# MysensorsDimmer.net
KiCad netlist of a schematic drawn in EAGLE
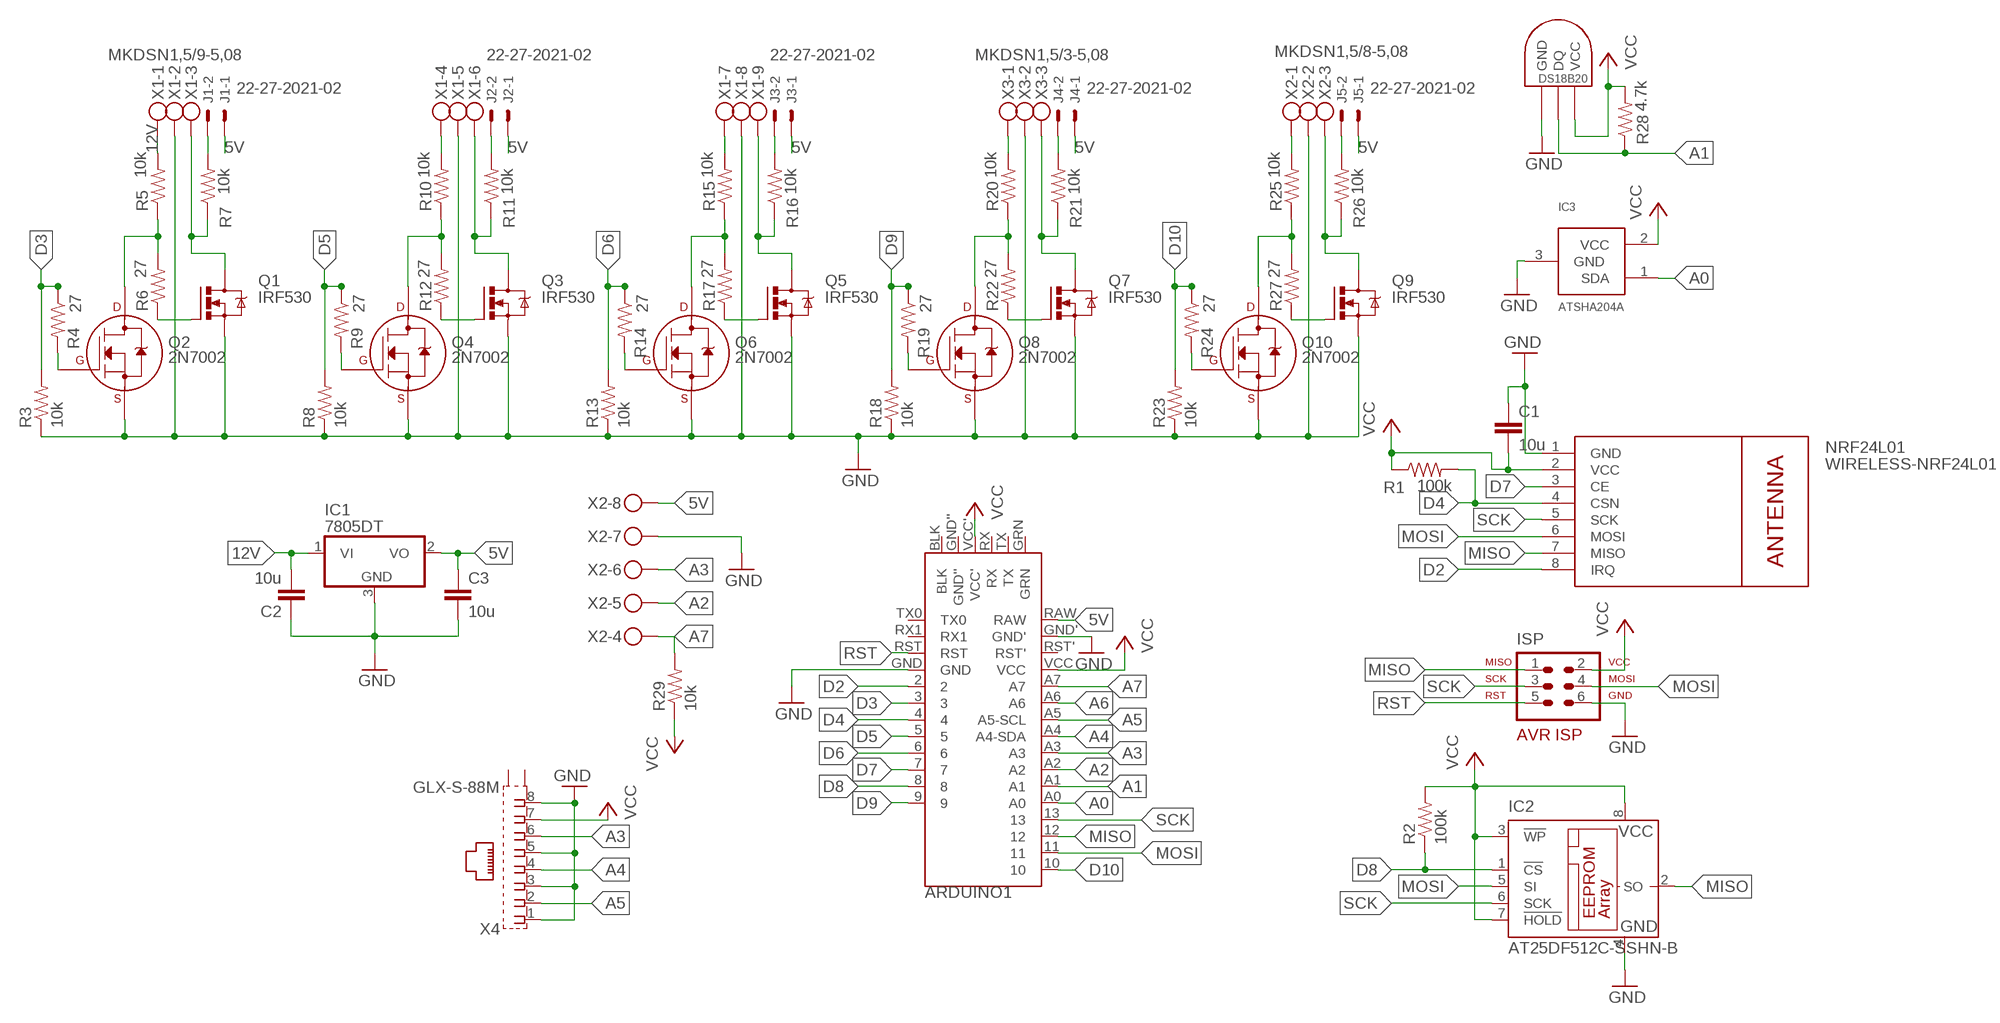
[diagram p0: schematic, sheet 1]

(export (version "E")
  (design (tool "Eeschema 10.0.6"))
  (components
    (comp (ref "ARDUINO1")
      (value "ARDUINO_PRO_MINI_V1")
      (footprint "eagle-import:ARDUINO_PRO_MINI_V1")
      (libsource (lib "eagle-import") (part "ARDUINO_PRO_MINI_V1"))
    )
    (comp (ref "C1")
      (value "10u")
      (footprint "eagle-import:0603-CAP")
      (libsource (lib "eagle-import") (part "CAP0603-CAP"))
    )
    (comp (ref "C2")
      (value "10u")
      (footprint "eagle-import:1206")
      (libsource (lib "eagle-import") (part "CAP1206"))
    )
    (comp (ref "C3")
      (value "10u")
      (footprint "eagle-import:0603-CAP")
      (libsource (lib "eagle-import") (part "CAP0603-CAP"))
    )
    (comp (ref "IC1")
      (value "7805DT")
      (footprint "eagle-import:TO252")
      (libsource (lib "eagle-import") (part "78DT05"))
    )
    (comp (ref "IC2")
      (value "AT25DF512C-SSHN-B")
      (footprint "eagle-import:SO-08")
      (fields (field (name "MF") "MICROCHIP") (field (name "MPN") "25AA080/SN"))
      (libsource (lib "eagle-import") (part "25SNAA080"))
    )
    (comp (ref "IC3")
      (value "ATSHA204A")
      (footprint "eagle-import:SOT23")
      (libsource (lib "eagle-import") (part "ATSHA204A"))
    )
    (comp (ref "IC4")
      (value "DS1820")
      (footprint "eagle-import:µSOP8")
      (libsource (lib "eagle-import") (part "DS1820"))
    )
    (comp (ref "ISP")
      (value "N/M")
      (footprint "eagle-import:AVR-ISP-6")
      (libsource (lib "eagle-import") (part "AVR-ISP-6VERT"))
    )
    (comp (ref "J1")
      (value "22-27-2021-02")
      (footprint "eagle-import:6410-02")
      (libsource (lib "eagle-import") (part "22-?-0227-2021"))
    )
    (comp (ref "J2")
      (value "22-27-2021-02")
      (footprint "eagle-import:6410-02")
      (libsource (lib "eagle-import") (part "22-?-0227-2021"))
    )
    (comp (ref "J3")
      (value "22-27-2021-02")
      (footprint "eagle-import:6410-02")
      (libsource (lib "eagle-import") (part "22-?-0227-2021"))
    )
    (comp (ref "J4")
      (value "22-27-2021-02")
      (footprint "eagle-import:6410-02")
      (libsource (lib "eagle-import") (part "22-?-0227-2021"))
    )
    (comp (ref "J5")
      (value "22-27-2021-02")
      (footprint "eagle-import:6410-02")
      (libsource (lib "eagle-import") (part "22-?-0227-2021"))
    )
    (comp (ref "NRF24L01")
      (value "WIRELESS-NRF24L01")
      (footprint "eagle-import:WIRELESS-NRF24L01")
      (libsource (lib "eagle-import") (part "WIRELESS-NRF24L01"))
    )
    (comp (ref "Q1")
      (value "IRF530")
      (footprint "eagle-import:TO220BV")
      (libsource (lib "eagle-import") (part "IRF530"))
    )
    (comp (ref "Q2")
      (value "2N7002")
      (footprint "eagle-import:SOT-23")
      (libsource (lib "eagle-import") (part "2N700_SOT232"))
    )
    (comp (ref "Q3")
      (value "IRF530")
      (footprint "eagle-import:TO220BV")
      (libsource (lib "eagle-import") (part "IRF530"))
    )
    (comp (ref "Q4")
      (value "2N7002")
      (footprint "eagle-import:SOT-23")
      (libsource (lib "eagle-import") (part "2N700_SOT232"))
    )
    (comp (ref "Q5")
      (value "IRF530")
      (footprint "eagle-import:TO220BV")
      (libsource (lib "eagle-import") (part "IRF530"))
    )
    (comp (ref "Q6")
      (value "2N7002")
      (footprint "eagle-import:SOT-23")
      (libsource (lib "eagle-import") (part "2N700_SOT232"))
    )
    (comp (ref "Q7")
      (value "IRF530")
      (footprint "eagle-import:TO220BV")
      (libsource (lib "eagle-import") (part "IRF530"))
    )
    (comp (ref "Q8")
      (value "2N7002")
      (footprint "eagle-import:SOT-23")
      (libsource (lib "eagle-import") (part "2N700_SOT232"))
    )
    (comp (ref "Q9")
      (value "IRF530")
      (footprint "eagle-import:TO220BV")
      (libsource (lib "eagle-import") (part "IRF530"))
    )
    (comp (ref "Q10")
      (value "2N7002")
      (footprint "eagle-import:SOT-23")
      (libsource (lib "eagle-import") (part "2N700_SOT232"))
    )
    (comp (ref "R1")
      (value "100k")
      (footprint "eagle-import:0603-RES")
      (libsource (lib "eagle-import") (part "RESISTOR0603-RES"))
    )
    (comp (ref "R2")
      (value "100k")
      (footprint "eagle-import:0603-RES")
      (libsource (lib "eagle-import") (part "RESISTOR0603-RES"))
    )
    (comp (ref "R3")
      (value "10k")
      (footprint "eagle-import:0603-RES")
      (libsource (lib "eagle-import") (part "RESISTOR0603-RES"))
    )
    (comp (ref "R4")
      (value "27")
      (footprint "eagle-import:0603-RES")
      (libsource (lib "eagle-import") (part "RESISTOR0603-RES"))
    )
    (comp (ref "R5")
      (value "10k")
      (footprint "eagle-import:0603-RES")
      (libsource (lib "eagle-import") (part "RESISTOR0603-RES"))
    )
    (comp (ref "R6")
      (value "27")
      (footprint "eagle-import:0603-RES")
      (libsource (lib "eagle-import") (part "RESISTOR0603-RES"))
    )
    (comp (ref "R7")
      (value "10k")
      (footprint "eagle-import:0603-RES")
      (libsource (lib "eagle-import") (part "RESISTOR0603-RES"))
    )
    (comp (ref "R8")
      (value "10k")
      (footprint "eagle-import:0603-RES")
      (libsource (lib "eagle-import") (part "RESISTOR0603-RES"))
    )
    (comp (ref "R9")
      (value "27")
      (footprint "eagle-import:0603-RES")
      (libsource (lib "eagle-import") (part "RESISTOR0603-RES"))
    )
    (comp (ref "R10")
      (value "10k")
      (footprint "eagle-import:0603-RES")
      (libsource (lib "eagle-import") (part "RESISTOR0603-RES"))
    )
    (comp (ref "R11")
      (value "10k")
      (footprint "eagle-import:0603-RES")
      (libsource (lib "eagle-import") (part "RESISTOR0603-RES"))
    )
    (comp (ref "R12")
      (value "27")
      (footprint "eagle-import:0603-RES")
      (libsource (lib "eagle-import") (part "RESISTOR0603-RES"))
    )
    (comp (ref "R13")
      (value "10k")
      (footprint "eagle-import:0603-RES")
      (libsource (lib "eagle-import") (part "RESISTOR0603-RES"))
    )
    (comp (ref "R14")
      (value "27")
      (footprint "eagle-import:0603-RES")
      (libsource (lib "eagle-import") (part "RESISTOR0603-RES"))
    )
    (comp (ref "R15")
      (value "10k")
      (footprint "eagle-import:0603-RES")
      (libsource (lib "eagle-import") (part "RESISTOR0603-RES"))
    )
    (comp (ref "R16")
      (value "10k")
      (footprint "eagle-import:0603-RES")
      (libsource (lib "eagle-import") (part "RESISTOR0603-RES"))
    )
    (comp (ref "R17")
      (value "27")
      (footprint "eagle-import:0603-RES")
      (libsource (lib "eagle-import") (part "RESISTOR0603-RES"))
    )
    (comp (ref "R18")
      (value "10k")
      (footprint "eagle-import:0603-RES")
      (libsource (lib "eagle-import") (part "RESISTOR0603-RES"))
    )
    (comp (ref "R19")
      (value "27")
      (footprint "eagle-import:0603-RES")
      (libsource (lib "eagle-import") (part "RESISTOR0603-RES"))
    )
    (comp (ref "R20")
      (value "10k")
      (footprint "eagle-import:0603-RES")
      (libsource (lib "eagle-import") (part "RESISTOR0603-RES"))
    )
    (comp (ref "R21")
      (value "10k")
      (footprint "eagle-import:0603-RES")
      (libsource (lib "eagle-import") (part "RESISTOR0603-RES"))
    )
    (comp (ref "R22")
      (value "27")
      (footprint "eagle-import:0603-RES")
      (libsource (lib "eagle-import") (part "RESISTOR0603-RES"))
    )
    (comp (ref "R23")
      (value "10k")
      (footprint "eagle-import:0603-RES")
      (libsource (lib "eagle-import") (part "RESISTOR0603-RES"))
    )
    (comp (ref "R24")
      (value "27")
      (footprint "eagle-import:0603-RES")
      (libsource (lib "eagle-import") (part "RESISTOR0603-RES"))
    )
    (comp (ref "R25")
      (value "10k")
      (footprint "eagle-import:0603-RES")
      (libsource (lib "eagle-import") (part "RESISTOR0603-RES"))
    )
    (comp (ref "R26")
      (value "10k")
      (footprint "eagle-import:0603-RES")
      (libsource (lib "eagle-import") (part "RESISTOR0603-RES"))
    )
    (comp (ref "R27")
      (value "27")
      (footprint "eagle-import:0603-RES")
      (libsource (lib "eagle-import") (part "RESISTOR0603-RES"))
    )
    (comp (ref "R28")
      (value "4.7k")
      (footprint "eagle-import:0603-RES")
      (libsource (lib "eagle-import") (part "RESISTOR0603-RES"))
    )
    (comp (ref "R29")
      (value "10k")
      (footprint "eagle-import:0603-RES")
      (libsource (lib "eagle-import") (part "RESISTOR0603-RES"))
    )
    (comp (ref "X1")
      (value "MKDSN1,5/9-5,08")
      (footprint "eagle-import:MKDSN1,5_9-5,08")
      (fields (field (name "MPN") "SMKDSN1,5/9-5,08"))
      (libsource (lib "eagle-import") (part "MKDSN1,5/9-5,08"))
    )
    (comp (ref "X2")
      (value "MKDSN1,5/8-5,08")
      (footprint "eagle-import:MKDSN1,5_8-5,08")
      (fields (field (name "MPN") "SMKDSN1,5/8-5,08"))
      (libsource (lib "eagle-import") (part "MKDSN1,5/8-5,08"))
    )
    (comp (ref "X3")
      (value "MKDSN1,5/3-5,08")
      (footprint "eagle-import:MKDSN1,5_3-5,08")
      (fields (field (name "MPN") "SMKDSN1,5/3-5,08"))
      (libsource (lib "eagle-import") (part "MKDSN1,5/3-5,08"))
    )
    (comp (ref "X4")
      (value "GLX-S-88M")
      (footprint "eagle-import:GLX-S-88M")
      (libsource (lib "eagle-import") (part "GLX-S-88M"))
    )
  )
  (nets
    (net (code "1") (name "5V") (class "Default")
      (node (ref "ARDUINO1") (pin "RAW") (pinfunction "RAW_RAW") (pintype "bidirectional"))
      (node (ref "C3") (pin "1") (pinfunction "1_1") (pintype "passive"))
      (node (ref "IC1") (pin "2") (pinfunction "VO_2") (pintype "passive"))
      (node (ref "J1") (pin "1") (pinfunction "S_1") (pintype "passive"))
      (node (ref "J2") (pin "1") (pinfunction "S_1") (pintype "passive"))
      (node (ref "J3") (pin "1") (pinfunction "S_1") (pintype "passive"))
      (node (ref "J4") (pin "1") (pinfunction "S_1") (pintype "passive"))
      (node (ref "J5") (pin "1") (pinfunction "S_1") (pintype "passive"))
      (node (ref "X2") (pin "8") (pinfunction "KL_8") (pintype "passive"))
    )
    (net (code "2") (name "12V") (class "Default")
      (node (ref "C2") (pin "2") (pinfunction "2_2") (pintype "passive"))
      (node (ref "IC1") (pin "1") (pinfunction "VI_1") (pintype "input"))
      (node (ref "R5") (pin "2") (pinfunction "2_2") (pintype "passive"))
      (node (ref "X1") (pin "1") (pinfunction "KL_1") (pintype "passive"))
    )
    (net (code "3") (name "A0") (class "Default")
      (node (ref "ARDUINO1") (pin "A0") (pinfunction "A0_A0") (pintype "bidirectional"))
      (node (ref "IC3") (pin "1") (pinfunction "SDA_1") (pintype "bidirectional"))
    )
    (net (code "4") (name "A1") (class "Default")
      (node (ref "ARDUINO1") (pin "A1") (pinfunction "A1_A1") (pintype "bidirectional"))
      (node (ref "IC4") (pin "1") (pinfunction "DQ_1") (pintype "bidirectional"))
      (node (ref "R28") (pin "1") (pinfunction "1_1") (pintype "passive"))
    )
    (net (code "5") (name "A2") (class "Default")
      (node (ref "ARDUINO1") (pin "A2") (pinfunction "A2_A2") (pintype "bidirectional"))
      (node (ref "X2") (pin "5") (pinfunction "KL_5") (pintype "passive"))
    )
    (net (code "6") (name "A3") (class "Default")
      (node (ref "ARDUINO1") (pin "A3") (pinfunction "A3_A3") (pintype "bidirectional"))
      (node (ref "X2") (pin "6") (pinfunction "KL_6") (pintype "passive"))
      (node (ref "X4") (pin "6") (pinfunction "6_6") (pintype "passive"))
    )
    (net (code "7") (name "A4") (class "Default")
      (node (ref "ARDUINO1") (pin "A4") (pinfunction "A4-SDA_A4") (pintype "bidirectional"))
      (node (ref "X4") (pin "4") (pinfunction "4_4") (pintype "passive"))
    )
    (net (code "8") (name "A5") (class "Default")
      (node (ref "ARDUINO1") (pin "A5") (pinfunction "A5-SCL_A5") (pintype "bidirectional"))
      (node (ref "X4") (pin "2") (pinfunction "2_2") (pintype "passive"))
    )
    (net (code "9") (name "A6") (class "Default")
      (node (ref "ARDUINO1") (pin "A6") (pinfunction "A6_A6") (pintype "bidirectional"))
    )
    (net (code "10") (name "A7") (class "Default")
      (node (ref "ARDUINO1") (pin "A7") (pinfunction "A7_A7") (pintype "bidirectional"))
      (node (ref "R29") (pin "2") (pinfunction "2_2") (pintype "passive"))
      (node (ref "X2") (pin "4") (pinfunction "KL_4") (pintype "passive"))
    )
    (net (code "11") (name "D2") (class "Default")
      (node (ref "ARDUINO1") (pin "2") (pinfunction "2_2") (pintype "bidirectional"))
      (node (ref "NRF24L01") (pin "8") (pinfunction "IRQ_8") (pintype "bidirectional"))
    )
    (net (code "12") (name "D3") (class "Default")
      (node (ref "ARDUINO1") (pin "3") (pinfunction "3_3") (pintype "bidirectional"))
      (node (ref "R3") (pin "2") (pinfunction "2_2") (pintype "passive"))
      (node (ref "R4") (pin "1") (pinfunction "1_1") (pintype "passive"))
    )
    (net (code "13") (name "D4") (class "Default")
      (node (ref "ARDUINO1") (pin "4") (pinfunction "4_4") (pintype "bidirectional"))
      (node (ref "NRF24L01") (pin "4") (pinfunction "CSN_4") (pintype "bidirectional"))
      (node (ref "R1") (pin "2") (pinfunction "2_2") (pintype "passive"))
    )
    (net (code "14") (name "D5") (class "Default")
      (node (ref "ARDUINO1") (pin "5") (pinfunction "5_5") (pintype "bidirectional"))
      (node (ref "R8") (pin "2") (pinfunction "2_2") (pintype "passive"))
      (node (ref "R9") (pin "1") (pinfunction "1_1") (pintype "passive"))
    )
    (net (code "15") (name "D6") (class "Default")
      (node (ref "ARDUINO1") (pin "6") (pinfunction "6_6") (pintype "bidirectional"))
      (node (ref "R13") (pin "2") (pinfunction "2_2") (pintype "passive"))
      (node (ref "R14") (pin "1") (pinfunction "1_1") (pintype "passive"))
    )
    (net (code "16") (name "D7") (class "Default")
      (node (ref "ARDUINO1") (pin "7") (pinfunction "7_7") (pintype "bidirectional"))
      (node (ref "NRF24L01") (pin "3") (pinfunction "CE_3") (pintype "bidirectional"))
    )
    (net (code "17") (name "D8") (class "Default")
      (node (ref "ARDUINO1") (pin "8") (pinfunction "8_8") (pintype "bidirectional"))
      (node (ref "IC2") (pin "1") (pinfunction "~{CS}_1") (pintype "input"))
      (node (ref "R2") (pin "1") (pinfunction "1_1") (pintype "passive"))
    )
    (net (code "18") (name "D9") (class "Default")
      (node (ref "ARDUINO1") (pin "9") (pinfunction "9_9") (pintype "bidirectional"))
      (node (ref "R18") (pin "2") (pinfunction "2_2") (pintype "passive"))
      (node (ref "R19") (pin "1") (pinfunction "1_1") (pintype "passive"))
    )
    (net (code "19") (name "D10") (class "Default")
      (node (ref "ARDUINO1") (pin "10") (pinfunction "10_10") (pintype "bidirectional"))
      (node (ref "R23") (pin "2") (pinfunction "2_2") (pintype "passive"))
      (node (ref "R24") (pin "1") (pinfunction "1_1") (pintype "passive"))
    )
    (net (code "20") (name "GND") (class "Default")
      (node (ref "ARDUINO1") (pin "GND") (pinfunction "GND_GND") (pintype "bidirectional"))
      (node (ref "ARDUINO1") (pin "GND'") (pinfunction "GND'_GND'") (pintype "bidirectional"))
      (node (ref "C1") (pin "1") (pinfunction "1_1") (pintype "passive"))
      (node (ref "C2") (pin "1") (pinfunction "1_1") (pintype "passive"))
      (node (ref "C3") (pin "2") (pinfunction "2_2") (pintype "passive"))
      (node (ref "IC1") (pin "3") (pinfunction "GND_3") (pintype "passive"))
      (node (ref "IC2") (pin "4") (pinfunction "GND_4") (pintype "power_in"))
      (node (ref "IC3") (pin "3") (pinfunction "GND_3") (pintype "bidirectional"))
      (node (ref "IC4") (pin "4") (pinfunction "GND_4") (pintype "power_in"))
      (node (ref "ISP") (pin "6") (pinfunction "6_6") (pintype "passive"))
      (node (ref "NRF24L01") (pin "1") (pinfunction "GND_1") (pintype "power_in"))
      (node (ref "Q1") (pin "S") (pinfunction "S_S") (pintype "passive"))
      (node (ref "Q10") (pin "2") (pinfunction "S_2") (pintype "bidirectional"))
      (node (ref "Q2") (pin "2") (pinfunction "S_2") (pintype "bidirectional"))
      (node (ref "Q3") (pin "S") (pinfunction "S_S") (pintype "passive"))
      (node (ref "Q4") (pin "2") (pinfunction "S_2") (pintype "bidirectional"))
      (node (ref "Q5") (pin "S") (pinfunction "S_S") (pintype "passive"))
      (node (ref "Q6") (pin "2") (pinfunction "S_2") (pintype "bidirectional"))
      (node (ref "Q7") (pin "S") (pinfunction "S_S") (pintype "passive"))
      (node (ref "Q8") (pin "2") (pinfunction "S_2") (pintype "bidirectional"))
      (node (ref "Q9") (pin "S") (pinfunction "S_S") (pintype "passive"))
      (node (ref "R13") (pin "1") (pinfunction "1_1") (pintype "passive"))
      (node (ref "R18") (pin "1") (pinfunction "1_1") (pintype "passive"))
      (node (ref "R23") (pin "1") (pinfunction "1_1") (pintype "passive"))
      (node (ref "R3") (pin "1") (pinfunction "1_1") (pintype "passive"))
      (node (ref "R8") (pin "1") (pinfunction "1_1") (pintype "passive"))
      (node (ref "X1") (pin "2") (pinfunction "KL_2") (pintype "passive"))
      (node (ref "X1") (pin "5") (pinfunction "KL_5") (pintype "passive"))
      (node (ref "X1") (pin "8") (pinfunction "KL_8") (pintype "passive"))
      (node (ref "X2") (pin "2") (pinfunction "KL_2") (pintype "passive"))
      (node (ref "X2") (pin "7") (pinfunction "KL_7") (pintype "passive"))
      (node (ref "X3") (pin "2") (pinfunction "KL_2") (pintype "passive"))
      (node (ref "X4") (pin "1") (pinfunction "1_1") (pintype "passive"))
      (node (ref "X4") (pin "3") (pinfunction "3_3") (pintype "passive"))
      (node (ref "X4") (pin "5") (pinfunction "5_5") (pintype "passive"))
      (node (ref "X4") (pin "8") (pinfunction "8_8") (pintype "passive"))
    )
    (net (code "21") (name "MISO") (class "Default")
      (node (ref "ARDUINO1") (pin "12") (pinfunction "12_12") (pintype "bidirectional"))
      (node (ref "IC2") (pin "2") (pinfunction "SO_2") (pintype "bidirectional"))
      (node (ref "ISP") (pin "1") (pinfunction "1_1") (pintype "passive"))
      (node (ref "NRF24L01") (pin "7") (pinfunction "MISO_7") (pintype "bidirectional"))
    )
    (net (code "22") (name "MOSI") (class "Default")
      (node (ref "ARDUINO1") (pin "11") (pinfunction "11_11") (pintype "bidirectional"))
      (node (ref "IC2") (pin "5") (pinfunction "SI_5") (pintype "input"))
      (node (ref "ISP") (pin "4") (pinfunction "4_4") (pintype "passive"))
      (node (ref "NRF24L01") (pin "6") (pinfunction "MOSI_6") (pintype "bidirectional"))
    )
    (net (code "23") (name "Net-(J1B-S)") (class "Default")
      (node (ref "J1") (pin "2") (pinfunction "S_2") (pintype "passive"))
      (node (ref "R7") (pin "2") (pinfunction "2_2") (pintype "passive"))
    )
    (net (code "24") (name "Net-(J2B-S)") (class "Default")
      (node (ref "J2") (pin "2") (pinfunction "S_2") (pintype "passive"))
      (node (ref "R11") (pin "2") (pinfunction "2_2") (pintype "passive"))
    )
    (net (code "25") (name "Net-(J3B-S)") (class "Default")
      (node (ref "J3") (pin "2") (pinfunction "S_2") (pintype "passive"))
      (node (ref "R16") (pin "2") (pinfunction "2_2") (pintype "passive"))
    )
    (net (code "26") (name "Net-(J4B-S)") (class "Default")
      (node (ref "J4") (pin "2") (pinfunction "S_2") (pintype "passive"))
      (node (ref "R21") (pin "2") (pinfunction "2_2") (pintype "passive"))
    )
    (net (code "27") (name "Net-(J5B-S)") (class "Default")
      (node (ref "J5") (pin "2") (pinfunction "S_2") (pintype "passive"))
      (node (ref "R26") (pin "2") (pinfunction "2_2") (pintype "passive"))
    )
    (net (code "28") (name "Net-(Q1-PadG)") (class "Default")
      (node (ref "Q1") (pin "G") (pinfunction "G_G") (pintype "passive"))
      (node (ref "R6") (pin "1") (pinfunction "1_1") (pintype "passive"))
    )
    (net (code "29") (name "Net-(Q2-D)") (class "Default")
      (node (ref "Q2") (pin "3") (pinfunction "D_3") (pintype "bidirectional"))
      (node (ref "R5") (pin "1") (pinfunction "1_1") (pintype "passive"))
      (node (ref "R6") (pin "2") (pinfunction "2_2") (pintype "passive"))
    )
    (net (code "30") (name "Net-(Q2-G)") (class "Default")
      (node (ref "Q2") (pin "1") (pinfunction "G_1") (pintype "tri_state"))
      (node (ref "R4") (pin "2") (pinfunction "2_2") (pintype "passive"))
    )
    (net (code "31") (name "Net-(Q3-PadG)") (class "Default")
      (node (ref "Q3") (pin "G") (pinfunction "G_G") (pintype "passive"))
      (node (ref "R12") (pin "1") (pinfunction "1_1") (pintype "passive"))
    )
    (net (code "32") (name "Net-(Q4-D)") (class "Default")
      (node (ref "Q4") (pin "3") (pinfunction "D_3") (pintype "bidirectional"))
      (node (ref "R10") (pin "1") (pinfunction "1_1") (pintype "passive"))
      (node (ref "R12") (pin "2") (pinfunction "2_2") (pintype "passive"))
    )
    (net (code "33") (name "Net-(Q4-G)") (class "Default")
      (node (ref "Q4") (pin "1") (pinfunction "G_1") (pintype "tri_state"))
      (node (ref "R9") (pin "2") (pinfunction "2_2") (pintype "passive"))
    )
    (net (code "34") (name "Net-(Q5-PadG)") (class "Default")
      (node (ref "Q5") (pin "G") (pinfunction "G_G") (pintype "passive"))
      (node (ref "R17") (pin "1") (pinfunction "1_1") (pintype "passive"))
    )
    (net (code "35") (name "Net-(Q6-D)") (class "Default")
      (node (ref "Q6") (pin "3") (pinfunction "D_3") (pintype "bidirectional"))
      (node (ref "R15") (pin "1") (pinfunction "1_1") (pintype "passive"))
      (node (ref "R17") (pin "2") (pinfunction "2_2") (pintype "passive"))
    )
    (net (code "36") (name "Net-(Q6-G)") (class "Default")
      (node (ref "Q6") (pin "1") (pinfunction "G_1") (pintype "tri_state"))
      (node (ref "R14") (pin "2") (pinfunction "2_2") (pintype "passive"))
    )
    (net (code "37") (name "Net-(Q7-PadG)") (class "Default")
      (node (ref "Q7") (pin "G") (pinfunction "G_G") (pintype "passive"))
      (node (ref "R22") (pin "1") (pinfunction "1_1") (pintype "passive"))
    )
    (net (code "38") (name "Net-(Q8-D)") (class "Default")
      (node (ref "Q8") (pin "3") (pinfunction "D_3") (pintype "bidirectional"))
      (node (ref "R20") (pin "1") (pinfunction "1_1") (pintype "passive"))
      (node (ref "R22") (pin "2") (pinfunction "2_2") (pintype "passive"))
    )
    (net (code "39") (name "Net-(Q8-G)") (class "Default")
      (node (ref "Q8") (pin "1") (pinfunction "G_1") (pintype "tri_state"))
      (node (ref "R19") (pin "2") (pinfunction "2_2") (pintype "passive"))
    )
    (net (code "40") (name "Net-(Q9-PadG)") (class "Default")
      (node (ref "Q9") (pin "G") (pinfunction "G_G") (pintype "passive"))
      (node (ref "R27") (pin "1") (pinfunction "1_1") (pintype "passive"))
    )
    (net (code "41") (name "Net-(Q10-D)") (class "Default")
      (node (ref "Q10") (pin "3") (pinfunction "D_3") (pintype "bidirectional"))
      (node (ref "R25") (pin "1") (pinfunction "1_1") (pintype "passive"))
      (node (ref "R27") (pin "2") (pinfunction "2_2") (pintype "passive"))
    )
    (net (code "42") (name "Net-(Q10-G)") (class "Default")
      (node (ref "Q10") (pin "1") (pinfunction "G_1") (pintype "tri_state"))
      (node (ref "R24") (pin "2") (pinfunction "2_2") (pintype "passive"))
    )
    (net (code "43") (name "Net-(X1C-KL)") (class "Default")
      (node (ref "Q1") (pin "D") (pinfunction "D_D") (pintype "passive"))
      (node (ref "R7") (pin "1") (pinfunction "1_1") (pintype "passive"))
      (node (ref "X1") (pin "3") (pinfunction "KL_3") (pintype "passive"))
    )
    (net (code "44") (name "Net-(X1D-KL)") (class "Default")
      (node (ref "R10") (pin "2") (pinfunction "2_2") (pintype "passive"))
      (node (ref "X1") (pin "4") (pinfunction "KL_4") (pintype "passive"))
    )
    (net (code "45") (name "Net-(X1F-KL)") (class "Default")
      (node (ref "Q3") (pin "D") (pinfunction "D_D") (pintype "passive"))
      (node (ref "R11") (pin "1") (pinfunction "1_1") (pintype "passive"))
      (node (ref "X1") (pin "6") (pinfunction "KL_6") (pintype "passive"))
    )
    (net (code "46") (name "Net-(X1G-KL)") (class "Default")
      (node (ref "R15") (pin "2") (pinfunction "2_2") (pintype "passive"))
      (node (ref "X1") (pin "7") (pinfunction "KL_7") (pintype "passive"))
    )
    (net (code "47") (name "Net-(X1I-KL)") (class "Default")
      (node (ref "Q5") (pin "D") (pinfunction "D_D") (pintype "passive"))
      (node (ref "R16") (pin "1") (pinfunction "1_1") (pintype "passive"))
      (node (ref "X1") (pin "9") (pinfunction "KL_9") (pintype "passive"))
    )
    (net (code "48") (name "Net-(X2A-KL)") (class "Default")
      (node (ref "R25") (pin "2") (pinfunction "2_2") (pintype "passive"))
      (node (ref "X2") (pin "1") (pinfunction "KL_1") (pintype "passive"))
    )
    (net (code "49") (name "Net-(X2C-KL)") (class "Default")
      (node (ref "Q9") (pin "D") (pinfunction "D_D") (pintype "passive"))
      (node (ref "R26") (pin "1") (pinfunction "1_1") (pintype "passive"))
      (node (ref "X2") (pin "3") (pinfunction "KL_3") (pintype "passive"))
    )
    (net (code "50") (name "Net-(X3A-KL)") (class "Default")
      (node (ref "R20") (pin "2") (pinfunction "2_2") (pintype "passive"))
      (node (ref "X3") (pin "1") (pinfunction "KL_1") (pintype "passive"))
    )
    (net (code "51") (name "Net-(X3C-KL)") (class "Default")
      (node (ref "Q7") (pin "D") (pinfunction "D_D") (pintype "passive"))
      (node (ref "R21") (pin "1") (pinfunction "1_1") (pintype "passive"))
      (node (ref "X3") (pin "3") (pinfunction "KL_3") (pintype "passive"))
    )
    (net (code "52") (name "RST") (class "Default")
      (node (ref "ARDUINO1") (pin "RST") (pinfunction "RST_RST") (pintype "bidirectional"))
      (node (ref "ISP") (pin "5") (pinfunction "5_5") (pintype "passive"))
    )
    (net (code "53") (name "SCK") (class "Default")
      (node (ref "ARDUINO1") (pin "13") (pinfunction "13_13") (pintype "bidirectional"))
      (node (ref "IC2") (pin "6") (pinfunction "SCK_6") (pintype "input"))
      (node (ref "ISP") (pin "3") (pinfunction "3_3") (pintype "passive"))
      (node (ref "NRF24L01") (pin "5") (pinfunction "SCK_5") (pintype "bidirectional"))
    )
    (net (code "54") (name "VCC") (class "Default")
      (node (ref "ARDUINO1") (pin "VCC") (pinfunction "VCC_VCC") (pintype "bidirectional"))
      (node (ref "ARDUINO1") (pin "VCC'") (pinfunction "VCC'_VCC'") (pintype "bidirectional"))
      (node (ref "C1") (pin "2") (pinfunction "2_2") (pintype "passive"))
      (node (ref "IC2") (pin "3") (pinfunction "~{WP}_3") (pintype "input"))
      (node (ref "IC2") (pin "7") (pinfunction "~{HOLD}_7") (pintype "input"))
      (node (ref "IC2") (pin "8") (pinfunction "VCC_8") (pintype "power_in"))
      (node (ref "IC3") (pin "2") (pinfunction "VCC_2") (pintype "bidirectional"))
      (node (ref "IC4") (pin "8") (pinfunction "VCC_8") (pintype "power_in"))
      (node (ref "ISP") (pin "2") (pinfunction "2_2") (pintype "passive"))
      (node (ref "NRF24L01") (pin "2") (pinfunction "VCC_2") (pintype "power_in"))
      (node (ref "R1") (pin "1") (pinfunction "1_1") (pintype "passive"))
      (node (ref "R2") (pin "2") (pinfunction "2_2") (pintype "passive"))
      (node (ref "R28") (pin "2") (pinfunction "2_2") (pintype "passive"))
      (node (ref "R29") (pin "1") (pinfunction "1_1") (pintype "passive"))
      (node (ref "X4") (pin "7") (pinfunction "7_7") (pintype "passive"))
    )
    (net (code "55") (name "unconnected-(ARDUINO1-PadBLK)") (class "Default")
      (node (ref "ARDUINO1") (pin "BLK") (pinfunction "BLK_BLK") (pintype "bidirectional"))
    )
    (net (code "56") (name "unconnected-(ARDUINO1-PadGND'')") (class "Default")
      (node (ref "ARDUINO1") (pin "GND''") (pinfunction "GND''_GND''") (pintype "bidirectional"))
    )
    (net (code "57") (name "unconnected-(ARDUINO1-PadGRN)") (class "Default")
      (node (ref "ARDUINO1") (pin "GRN") (pinfunction "GRN_GRN") (pintype "bidirectional"))
    )
    (net (code "58") (name "unconnected-(ARDUINO1-PadRST')") (class "Default")
      (node (ref "ARDUINO1") (pin "RST'") (pinfunction "RST'_RST'") (pintype "bidirectional"))
    )
    (net (code "59") (name "unconnected-(ARDUINO1-PadRX)") (class "Default")
      (node (ref "ARDUINO1") (pin "RX") (pinfunction "RX_RX") (pintype "bidirectional"))
    )
    (net (code "60") (name "unconnected-(ARDUINO1-PadRX1)") (class "Default")
      (node (ref "ARDUINO1") (pin "RX1") (pinfunction "RX1_RX1") (pintype "bidirectional"))
    )
    (net (code "61") (name "unconnected-(ARDUINO1-PadTX)") (class "Default")
      (node (ref "ARDUINO1") (pin "TX") (pinfunction "TX_TX") (pintype "bidirectional"))
    )
    (net (code "62") (name "unconnected-(ARDUINO1-PadTX0)") (class "Default")
      (node (ref "ARDUINO1") (pin "TX0") (pinfunction "TX0_TX0") (pintype "bidirectional"))
    )
    (net (code "63") (name "unconnected-(X4-PadS1)") (class "Default")
      (node (ref "X4") (pin "S1") (pinfunction "S1_S1") (pintype "passive"))
    )
    (net (code "64") (name "unconnected-(X4-PadS2)") (class "Default")
      (node (ref "X4") (pin "S2") (pinfunction "S2_S2") (pintype "passive"))
    )
  )
)
